# tent1.net
KiCad netlist of a schematic drawn in EAGLE
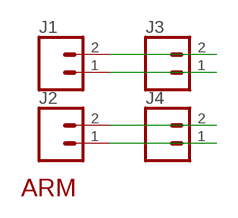
[diagram p0: schematic, sheet 1]

(export (version "E")
  (design (tool "Eeschema 10.0.6"))
  (components
    (comp (ref "J1")
      (value "CONN_02LOCK")
      (footprint "eagle-import:1X02_LOCK")
      (libsource (lib "eagle-import") (part "CONN_02LOCK"))
    )
    (comp (ref "J2")
      (value "CONN_02LOCK")
      (footprint "eagle-import:1X02_LOCK")
      (libsource (lib "eagle-import") (part "CONN_02LOCK"))
    )
    (comp (ref "J3")
      (value "CONN_02LOCK")
      (footprint "eagle-import:1X02_LOCK")
      (libsource (lib "eagle-import") (part "CONN_02LOCK"))
    )
    (comp (ref "J4")
      (value "CONN_02LOCK")
      (footprint "eagle-import:1X02_LOCK")
      (libsource (lib "eagle-import") (part "CONN_02LOCK"))
    )
    (comp (ref "U$1")
      (value "ARMTENT1")
      (footprint "eagle-import:TENT1")
      (libsource (lib "eagle-import") (part "ARMTENT1"))
    )
  )
  (nets
    (net (code "1") (name "Net-(J1-Pad1)") (class "Default")
      (node (ref "J1") (pin "1") (pinfunction "1_1") (pintype "passive"))
      (node (ref "J3") (pin "1") (pinfunction "1_1") (pintype "passive"))
    )
    (net (code "2") (name "Net-(J1-Pad2)") (class "Default")
      (node (ref "J1") (pin "2") (pinfunction "2_2") (pintype "passive"))
      (node (ref "J3") (pin "2") (pinfunction "2_2") (pintype "passive"))
    )
    (net (code "3") (name "Net-(J2-Pad1)") (class "Default")
      (node (ref "J2") (pin "1") (pinfunction "1_1") (pintype "passive"))
      (node (ref "J4") (pin "1") (pinfunction "1_1") (pintype "passive"))
    )
    (net (code "4") (name "Net-(J2-Pad2)") (class "Default")
      (node (ref "J2") (pin "2") (pinfunction "2_2") (pintype "passive"))
      (node (ref "J4") (pin "2") (pinfunction "2_2") (pintype "passive"))
    )
  )
)
